# HDMI.net
KiCad netlist of a schematic drawn in Altium Designer
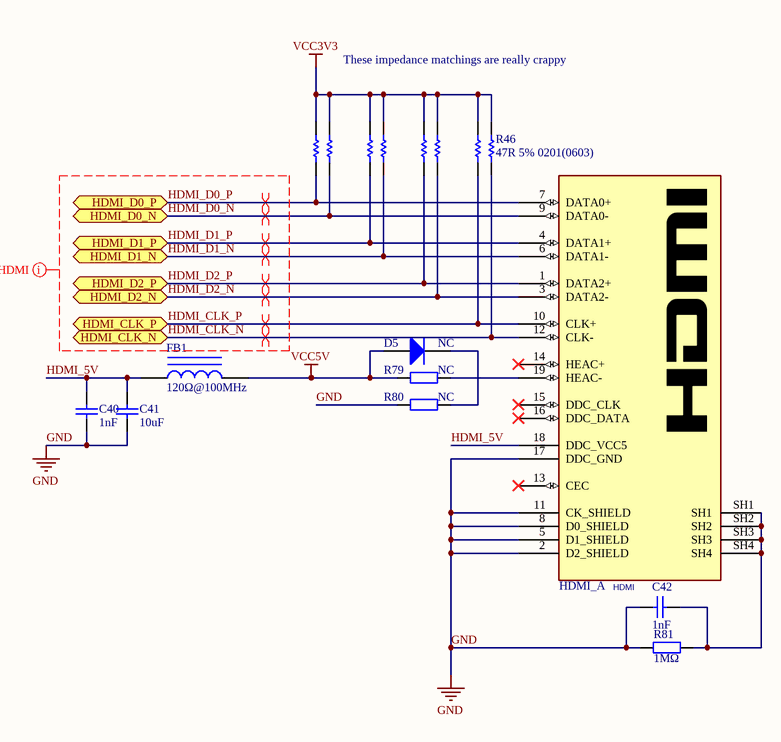
[diagram p0: HDMI.SchDoc]

(export (version "E")
  (design (tool "Eeschema 10.0.6"))
  (components
    (comp (ref "C40")
      (value "1nF")
      (footprint "0805_C")
      (description "贴片电容")
      (libsource (lib "Cap") (part "0805 1nF (102) 10% 50V"))
    )
    (comp (ref "C41")
      (value "10uF")
      (footprint "0603_C")
      (description "贴片电容")
      (libsource (lib "Cap") (part "0603 10uF (106) 10% 10V"))
    )
    (comp (ref "C42")
      (value "1nF")
      (footprint "0805_C")
      (description "贴片电容")
      (libsource (lib "Cap") (part "0805 1nF (102) 10% 50V"))
    )
    (comp (ref "D5")
      (value "NC")
      (footprint "SMA(DO-214AC)_S1")
      (description "二极管 TVS")
      (libsource (lib "Diode") (part "SMA(DO-214AC) SS210"))
    )
    (comp (ref "FB1")
      (value "120Ω@100MHz")
      (footprint "0805_L")
      (description "贴片磁珠")
      (libsource (lib "IUD") (part "0805 600Ω 25% 100MHz"))
    )
    (comp (ref "HDMI")
      (value "HDMI_A")
      (footprint "HDMI_A")
      (description "CONN, HDMI, Receptacle, TYPE A, 19P, RIGH-ANGLE")
      (fields
        (field (name "MANF") "Molex, WURTH")
        (field (name "MANF_P#") "47151-0001, 500254-1927, 685119134923")
      )
      (libsource (lib "Connector Display") (part "CONN_HDMI_A"))
    )
    (comp (ref "R35")
      (value "47R 5% 0201(0603)")
      (footprint "RESC0201(0603)_N")
      (description "47R 0.05W 5% 0201 (0603 Metric)  SMD")
      (fields (field (name "POWER") "0.05 W") (field (name "TOLERANCE") "5 %"))
      (libsource (lib "Altium Content Vault") (part "RES"))
    )
    (comp (ref "R36")
      (value "47R 5% 0201(0603)")
      (footprint "RESC0201(0603)_N")
      (description "47R 0.05W 5% 0201 (0603 Metric)  SMD")
      (fields (field (name "POWER") "0.05 W") (field (name "TOLERANCE") "5 %"))
      (libsource (lib "Altium Content Vault") (part "RES"))
    )
    (comp (ref "R39")
      (value "47R 5% 0201(0603)")
      (footprint "RESC0201(0603)_N")
      (description "47R 0.05W 5% 0201 (0603 Metric)  SMD")
      (fields (field (name "POWER") "0.05 W") (field (name "TOLERANCE") "5 %"))
      (libsource (lib "Altium Content Vault") (part "RES"))
    )
    (comp (ref "R41")
      (value "47R 5% 0201(0603)")
      (footprint "RESC0201(0603)_N")
      (description "47R 0.05W 5% 0201 (0603 Metric)  SMD")
      (fields (field (name "POWER") "0.05 W") (field (name "TOLERANCE") "5 %"))
      (libsource (lib "Altium Content Vault") (part "RES"))
    )
    (comp (ref "R43")
      (value "47R 5% 0201(0603)")
      (footprint "RESC0201(0603)_N")
      (description "47R 0.05W 5% 0201 (0603 Metric)  SMD")
      (fields (field (name "POWER") "0.05 W") (field (name "TOLERANCE") "5 %"))
      (libsource (lib "Altium Content Vault") (part "RES"))
    )
    (comp (ref "R44")
      (value "47R 5% 0201(0603)")
      (footprint "RESC0201(0603)_N")
      (description "47R 0.05W 5% 0201 (0603 Metric)  SMD")
      (fields (field (name "POWER") "0.05 W") (field (name "TOLERANCE") "5 %"))
      (libsource (lib "Altium Content Vault") (part "RES"))
    )
    (comp (ref "R45")
      (value "47R 5% 0201(0603)")
      (footprint "RESC0201(0603)_N")
      (description "47R 0.05W 5% 0201 (0603 Metric)  SMD")
      (fields (field (name "POWER") "0.05 W") (field (name "TOLERANCE") "5 %"))
      (libsource (lib "Altium Content Vault") (part "RES"))
    )
    (comp (ref "R46")
      (value "47R 5% 0201(0603)")
      (footprint "RESC0201(0603)_N")
      (description "47R 0.05W 5% 0201 (0603 Metric)  SMD")
      (fields (field (name "POWER") "0.05 W") (field (name "TOLERANCE") "5 %"))
      (libsource (lib "Altium Content Vault") (part "RES"))
    )
    (comp (ref "R79")
      (value "NC")
      (footprint "0805_R")
      (description "贴片电阻")
      (libsource (lib "RES") (part "0805 1MΩ (1004) 1%"))
    )
    (comp (ref "R80")
      (value "NC")
      (footprint "0805_R")
      (description "贴片电阻")
      (libsource (lib "RES") (part "0805 1MΩ (1004) 1%"))
    )
    (comp (ref "R81")
      (value "1MΩ")
      (footprint "0805_R")
      (description "贴片电阻")
      (libsource (lib "RES") (part "0805 1MΩ (1004) 1%"))
    )
  )
  (nets
    (net (code "1") (name "/HDMI_5V") (class "Default")
      (node (ref "C40") (pin "1") (pinfunction "1_1") (pintype "passive"))
      (node (ref "C41") (pin "2") (pinfunction "2_2") (pintype "passive"))
      (node (ref "FB1") (pin "1") (pinfunction "1_1") (pintype "passive"))
      (node (ref "HDMI") (pin "18") (pinfunction "DDC_VCC5_18") (pintype "passive"))
    )
    (net (code "2") (name "/HDMI_CLK_N") (class "Default")
      (node (ref "HDMI") (pin "12") (pinfunction "CLK-_12") (pintype "bidirectional"))
      (node (ref "R46") (pin "1") (pinfunction "1_1") (pintype "passive"))
    )
    (net (code "3") (name "/HDMI_CLK_P") (class "Default")
      (node (ref "HDMI") (pin "10") (pinfunction "CLK+_10") (pintype "bidirectional"))
      (node (ref "R45") (pin "1") (pinfunction "1_1") (pintype "passive"))
    )
    (net (code "4") (name "/HDMI_D0_N") (class "Default")
      (node (ref "HDMI") (pin "9") (pinfunction "DATA0-_9") (pintype "bidirectional"))
      (node (ref "R36") (pin "1") (pinfunction "1_1") (pintype "passive"))
    )
    (net (code "5") (name "/HDMI_D0_P") (class "Default")
      (node (ref "HDMI") (pin "7") (pinfunction "DATA0+_7") (pintype "bidirectional"))
      (node (ref "R35") (pin "1") (pinfunction "1_1") (pintype "passive"))
    )
    (net (code "6") (name "/HDMI_D1_N") (class "Default")
      (node (ref "HDMI") (pin "6") (pinfunction "DATA1-_6") (pintype "bidirectional"))
      (node (ref "R41") (pin "1") (pinfunction "1_1") (pintype "passive"))
    )
    (net (code "7") (name "/HDMI_D1_P") (class "Default")
      (node (ref "HDMI") (pin "4") (pinfunction "DATA1+_4") (pintype "bidirectional"))
      (node (ref "R39") (pin "1") (pinfunction "1_1") (pintype "passive"))
    )
    (net (code "8") (name "/HDMI_D2_N") (class "Default")
      (node (ref "HDMI") (pin "3") (pinfunction "DATA2-_3") (pintype "bidirectional"))
      (node (ref "R44") (pin "1") (pinfunction "1_1") (pintype "passive"))
    )
    (net (code "9") (name "/HDMI_D2_P") (class "Default")
      (node (ref "HDMI") (pin "1") (pinfunction "DATA2+_1") (pintype "bidirectional"))
      (node (ref "R43") (pin "1") (pinfunction "1_1") (pintype "passive"))
    )
    (net (code "10") (name "GND") (class "Default")
      (node (ref "C40") (pin "2") (pinfunction "2_2") (pintype "passive"))
      (node (ref "C41") (pin "1") (pinfunction "1_1") (pintype "passive"))
      (node (ref "C42") (pin "2") (pinfunction "2_2") (pintype "passive"))
      (node (ref "HDMI") (pin "11") (pinfunction "CK_SHIELD_11") (pintype "passive"))
      (node (ref "HDMI") (pin "17") (pinfunction "DDC_GND_17") (pintype "passive"))
      (node (ref "HDMI") (pin "2") (pinfunction "D2_SHIELD_2") (pintype "passive"))
      (node (ref "HDMI") (pin "5") (pinfunction "D1_SHIELD_5") (pintype "passive"))
      (node (ref "HDMI") (pin "8") (pinfunction "D0_SHIELD_8") (pintype "passive"))
      (node (ref "R80") (pin "2") (pinfunction "2_2") (pintype "passive"))
      (node (ref "R81") (pin "2") (pinfunction "2_2") (pintype "passive"))
    )
    (net (code "11") (name "Net-(C42-Pad1)") (class "Default")
      (node (ref "C42") (pin "1") (pinfunction "1_1") (pintype "passive"))
      (node (ref "HDMI") (pin "SH1") (pinfunction "SH1_SH1") (pintype "passive"))
      (node (ref "HDMI") (pin "SH2") (pinfunction "SH2_SH2") (pintype "passive"))
      (node (ref "HDMI") (pin "SH3") (pinfunction "SH3_SH3") (pintype "passive"))
      (node (ref "HDMI") (pin "SH4") (pinfunction "SH4_SH4") (pintype "passive"))
      (node (ref "R81") (pin "1") (pinfunction "1_1") (pintype "passive"))
    )
    (net (code "12") (name "Net-(D5-K)") (class "Default")
      (node (ref "D5") (pin "2") (pinfunction "K_2") (pintype "passive"))
      (node (ref "R80") (pin "1") (pinfunction "1_1") (pintype "passive"))
    )
    (net (code "13") (name "Net-(HDMI-HEAC-)") (class "Default")
      (node (ref "HDMI") (pin "19") (pinfunction "HEAC-_19") (pintype "bidirectional"))
      (node (ref "R79") (pin "1") (pinfunction "1_1") (pintype "passive"))
    )
    (net (code "14") (name "VCC3V3") (class "Default")
      (node (ref "R35") (pin "2") (pinfunction "2_2") (pintype "passive"))
      (node (ref "R36") (pin "2") (pinfunction "2_2") (pintype "passive"))
      (node (ref "R39") (pin "2") (pinfunction "2_2") (pintype "passive"))
      (node (ref "R41") (pin "2") (pinfunction "2_2") (pintype "passive"))
      (node (ref "R43") (pin "2") (pinfunction "2_2") (pintype "passive"))
      (node (ref "R44") (pin "2") (pinfunction "2_2") (pintype "passive"))
      (node (ref "R45") (pin "2") (pinfunction "2_2") (pintype "passive"))
      (node (ref "R46") (pin "2") (pinfunction "2_2") (pintype "passive"))
    )
    (net (code "15") (name "VCC5V") (class "Default")
      (node (ref "D5") (pin "1") (pinfunction "A_1") (pintype "passive"))
      (node (ref "FB1") (pin "2") (pinfunction "2_2") (pintype "passive"))
      (node (ref "R79") (pin "2") (pinfunction "2_2") (pintype "passive"))
    )
    (net (code "16") (name "unconnected-(HDMI-CEC-Pad13)") (class "Default")
      (node (ref "HDMI") (pin "13") (pinfunction "CEC_13") (pintype "bidirectional+no_connect"))
    )
    (net (code "17") (name "unconnected-(HDMI-DDC_CLK-Pad15)") (class "Default")
      (node (ref "HDMI") (pin "15") (pinfunction "DDC_CLK_15") (pintype "bidirectional+no_connect"))
    )
    (net (code "18") (name "unconnected-(HDMI-DDC_DATA-Pad16)") (class "Default")
      (node (ref "HDMI") (pin "16") (pinfunction "DDC_DATA_16") (pintype "bidirectional+no_connect"))
    )
    (net (code "19") (name "unconnected-(HDMI-HEAC+-Pad14)") (class "Default")
      (node (ref "HDMI") (pin "14") (pinfunction "HEAC+_14") (pintype "bidirectional+no_connect"))
    )
  )
)
